# driver.net
KiCad netlist of a schematic drawn in EAGLE
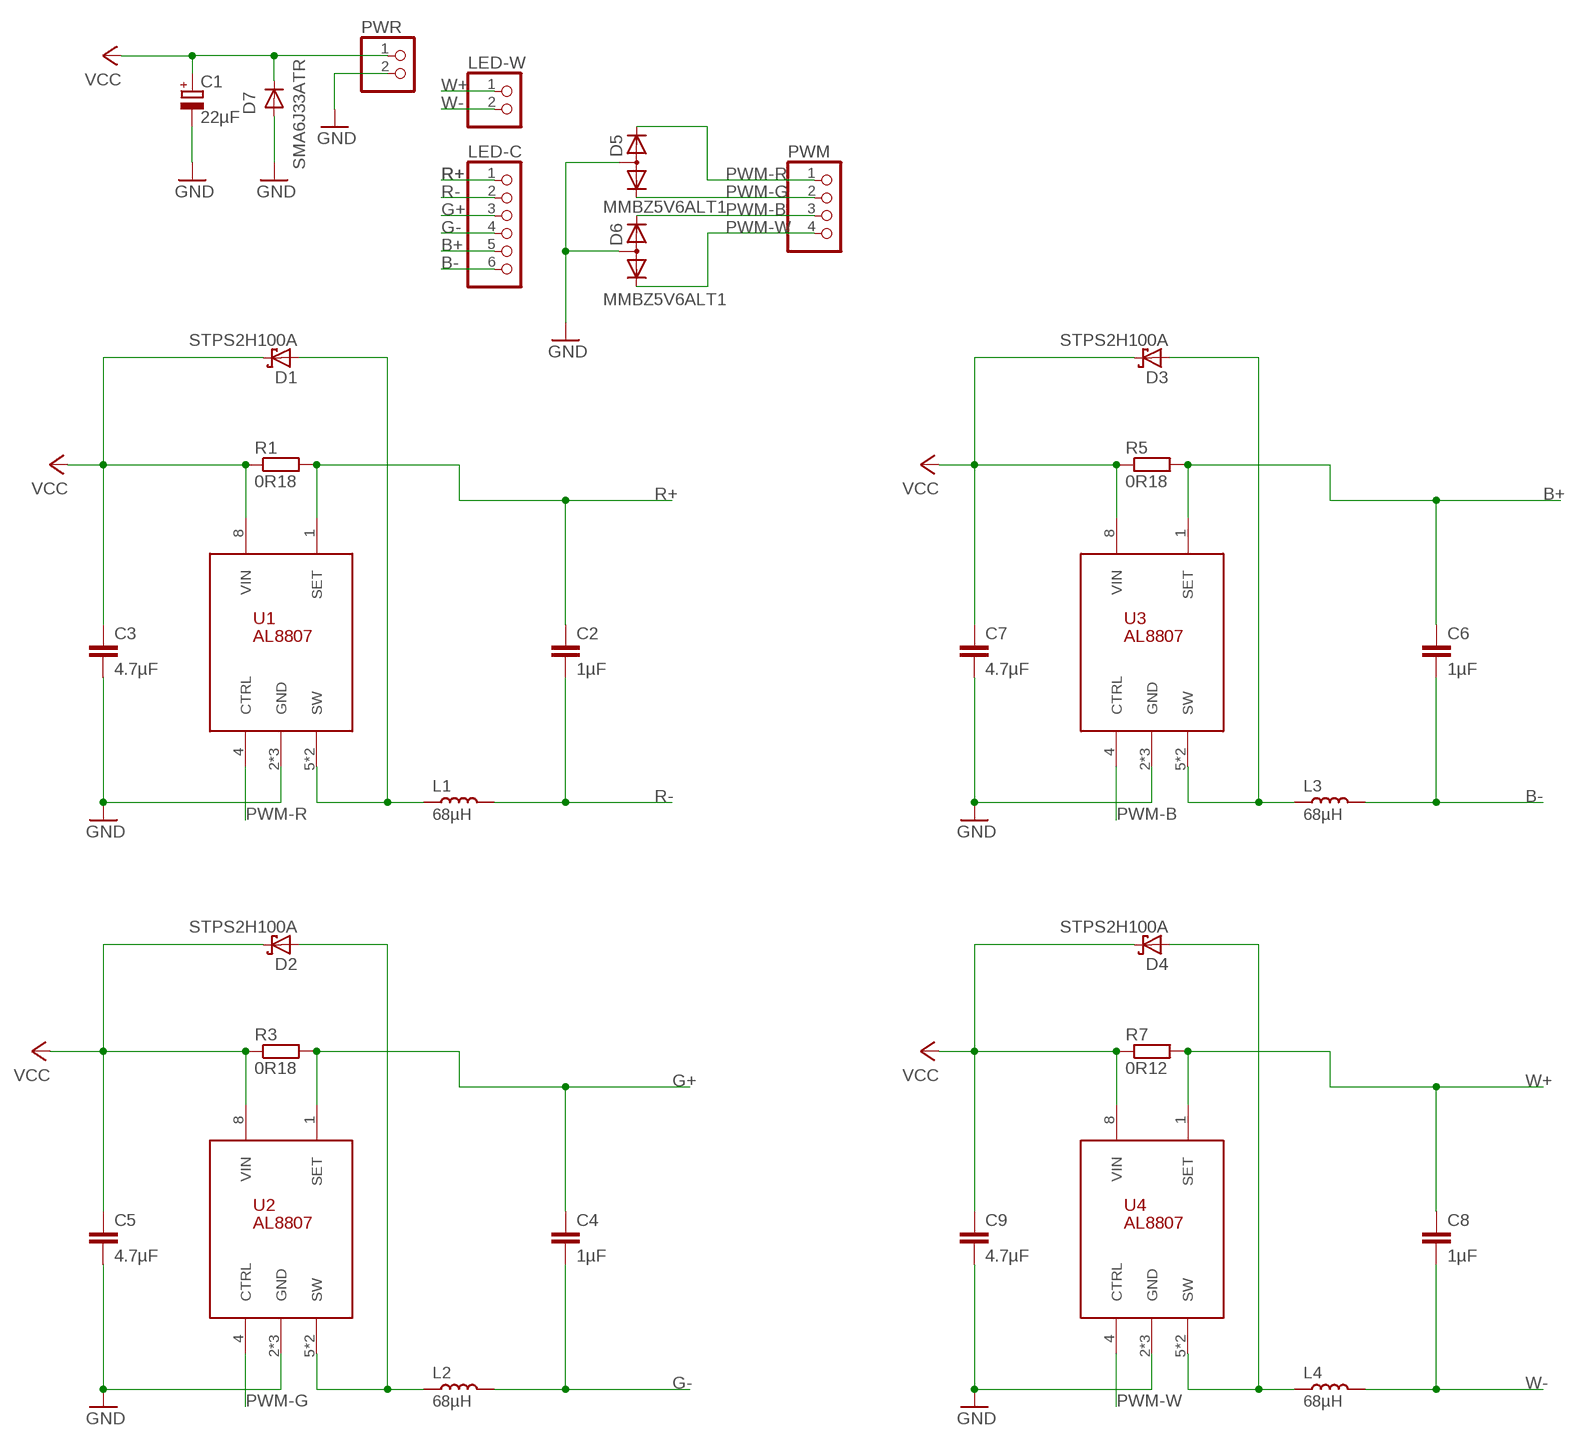
[diagram p0: schematic, sheet 1]

(export (version "E")
  (design (tool "Eeschema 10.0.6"))
  (components
    (comp (ref "C1")
      (value "22µF")
      (footprint "eagle-import:E2-5")
      (libsource (lib "eagle-import") (part "CPOL-EUE2-5"))
    )
    (comp (ref "C2")
      (value "1µF")
      (footprint "eagle-import:C1206")
      (libsource (lib "eagle-import") (part "C-EUC1206"))
    )
    (comp (ref "C3")
      (value "4.7µF")
      (footprint "eagle-import:C1206")
      (libsource (lib "eagle-import") (part "C-EUC1206"))
    )
    (comp (ref "C4")
      (value "1µF")
      (footprint "eagle-import:C1206")
      (libsource (lib "eagle-import") (part "C-EUC1206"))
    )
    (comp (ref "C5")
      (value "4.7µF")
      (footprint "eagle-import:C1206")
      (libsource (lib "eagle-import") (part "C-EUC1206"))
    )
    (comp (ref "C6")
      (value "1µF")
      (footprint "eagle-import:C1206")
      (libsource (lib "eagle-import") (part "C-EUC1206"))
    )
    (comp (ref "C7")
      (value "4.7µF")
      (footprint "eagle-import:C1206")
      (libsource (lib "eagle-import") (part "C-EUC1206"))
    )
    (comp (ref "C8")
      (value "1µF")
      (footprint "eagle-import:C1206")
      (libsource (lib "eagle-import") (part "C-EUC1206"))
    )
    (comp (ref "C9")
      (value "4.7µF")
      (footprint "eagle-import:C1206")
      (libsource (lib "eagle-import") (part "C-EUC1206"))
    )
    (comp (ref "D1")
      (value "STPS2H100A")
      (footprint "eagle-import:ST-DO-214AC")
      (fields (field (name "FARNELL_PART_NUMBER") "1467551"))
      (libsource (lib "eagle-import") (part "STPS2H100A"))
    )
    (comp (ref "D2")
      (value "STPS2H100A")
      (footprint "eagle-import:ST-DO-214AC")
      (fields (field (name "FARNELL_PART_NUMBER") "1467551"))
      (libsource (lib "eagle-import") (part "STPS2H100A"))
    )
    (comp (ref "D3")
      (value "STPS2H100A")
      (footprint "eagle-import:ST-DO-214AC")
      (fields (field (name "FARNELL_PART_NUMBER") "1467551"))
      (libsource (lib "eagle-import") (part "STPS2H100A"))
    )
    (comp (ref "D4")
      (value "STPS2H100A")
      (footprint "eagle-import:ST-DO-214AC")
      (fields (field (name "FARNELL_PART_NUMBER") "1467551"))
      (libsource (lib "eagle-import") (part "STPS2H100A"))
    )
    (comp (ref "D5")
      (value "MMBZ5V6ALT1")
      (footprint "eagle-import:SOT23")
      (libsource (lib "eagle-import") (part "DIODE-2CA|ACSOT23"))
    )
    (comp (ref "D6")
      (value "MMBZ5V6ALT1")
      (footprint "eagle-import:SOT23")
      (libsource (lib "eagle-import") (part "DIODE-2CA|ACSOT23"))
    )
    (comp (ref "D7")
      (value "SMA6J33ATR")
      (footprint "eagle-import:DO-214AC")
      (libsource (lib "eagle-import") (part "DIODE-DO-214AC"))
    )
    (comp (ref "L1")
      (value "68µH")
      (footprint "eagle-import:SRR1260")
      (libsource (lib "eagle-import") (part "INDUCTOR-SRR1260"))
    )
    (comp (ref "L2")
      (value "68µH")
      (footprint "eagle-import:SRR1260")
      (libsource (lib "eagle-import") (part "INDUCTOR-SRR1260"))
    )
    (comp (ref "L3")
      (value "68µH")
      (footprint "eagle-import:SRR1260")
      (libsource (lib "eagle-import") (part "INDUCTOR-SRR1260"))
    )
    (comp (ref "L4")
      (value "68µH")
      (footprint "eagle-import:SRR1260")
      (libsource (lib "eagle-import") (part "INDUCTOR-SRR1260"))
    )
    (comp (ref "LED-C")
      (value "PINHD-1X6")
      (footprint "eagle-import:1X06")
      (libsource (lib "eagle-import") (part "PINHD-1X6"))
    )
    (comp (ref "LED-W")
      (value "PINHD-1X2")
      (footprint "eagle-import:1X02")
      (libsource (lib "eagle-import") (part "PINHD-1X2"))
    )
    (comp (ref "PWM")
      (value "PINHD-1X4")
      (footprint "eagle-import:1X04")
      (libsource (lib "eagle-import") (part "PINHD-1X4"))
    )
    (comp (ref "PWR")
      (value "PINHD-1X2")
      (footprint "eagle-import:1X02")
      (libsource (lib "eagle-import") (part "PINHD-1X2"))
    )
    (comp (ref "R1")
      (value "0R18")
      (footprint "eagle-import:R0805")
      (libsource (lib "eagle-import") (part "R-EU_R0805"))
    )
    (comp (ref "R3")
      (value "0R18")
      (footprint "eagle-import:R0805")
      (libsource (lib "eagle-import") (part "R-EU_R0805"))
    )
    (comp (ref "R5")
      (value "0R18")
      (footprint "eagle-import:R0805")
      (libsource (lib "eagle-import") (part "R-EU_R0805"))
    )
    (comp (ref "R7")
      (value "0R12")
      (footprint "eagle-import:R0805")
      (libsource (lib "eagle-import") (part "R-EU_R0805"))
    )
    (comp (ref "U1")
      (value "AL8807")
      (footprint "eagle-import:MSOP-8EP")
      (libsource (lib "eagle-import") (part "AL8807"))
    )
    (comp (ref "U2")
      (value "AL8807")
      (footprint "eagle-import:MSOP-8EP")
      (libsource (lib "eagle-import") (part "AL8807"))
    )
    (comp (ref "U3")
      (value "AL8807")
      (footprint "eagle-import:MSOP-8EP")
      (libsource (lib "eagle-import") (part "AL8807"))
    )
    (comp (ref "U4")
      (value "AL8807")
      (footprint "eagle-import:MSOP-8EP")
      (libsource (lib "eagle-import") (part "AL8807"))
    )
  )
  (nets
    (net (code "1") (name "/B+") (class "Default")
      (node (ref "C6") (pin "1") (pinfunction "1_1") (pintype "passive"))
      (node (ref "LED-C") (pin "5") (pinfunction "5_5") (pintype "passive"))
      (node (ref "R5") (pin "2") (pinfunction "2_2") (pintype "passive"))
      (node (ref "U3") (pin "1") (pinfunction "SET_1") (pintype "bidirectional"))
    )
    (net (code "2") (name "/B-") (class "Default")
      (node (ref "C6") (pin "2") (pinfunction "2_2") (pintype "passive"))
      (node (ref "L3") (pin "2") (pinfunction "2_2") (pintype "passive"))
      (node (ref "LED-C") (pin "6") (pinfunction "6_6") (pintype "passive"))
    )
    (net (code "3") (name "/G+") (class "Default")
      (node (ref "C4") (pin "1") (pinfunction "1_1") (pintype "passive"))
      (node (ref "LED-C") (pin "3") (pinfunction "3_3") (pintype "passive"))
      (node (ref "R3") (pin "2") (pinfunction "2_2") (pintype "passive"))
      (node (ref "U2") (pin "1") (pinfunction "SET_1") (pintype "bidirectional"))
    )
    (net (code "4") (name "/G-") (class "Default")
      (node (ref "C4") (pin "2") (pinfunction "2_2") (pintype "passive"))
      (node (ref "L2") (pin "2") (pinfunction "2_2") (pintype "passive"))
      (node (ref "LED-C") (pin "4") (pinfunction "4_4") (pintype "passive"))
    )
    (net (code "5") (name "/PWM-B") (class "Default")
      (node (ref "D6") (pin "2") (pinfunction "K2_2") (pintype "passive"))
      (node (ref "PWM") (pin "3") (pinfunction "3_3") (pintype "passive"))
      (node (ref "U3") (pin "4") (pinfunction "CTRL_4") (pintype "bidirectional"))
    )
    (net (code "6") (name "/PWM-G") (class "Default")
      (node (ref "D5") (pin "1") (pinfunction "K1_1") (pintype "passive"))
      (node (ref "PWM") (pin "2") (pinfunction "2_2") (pintype "passive"))
      (node (ref "U2") (pin "4") (pinfunction "CTRL_4") (pintype "bidirectional"))
    )
    (net (code "7") (name "/PWM-R") (class "Default")
      (node (ref "D5") (pin "2") (pinfunction "K2_2") (pintype "passive"))
      (node (ref "PWM") (pin "1") (pinfunction "1_1") (pintype "passive"))
      (node (ref "U1") (pin "4") (pinfunction "CTRL_4") (pintype "bidirectional"))
    )
    (net (code "8") (name "/PWM-W") (class "Default")
      (node (ref "D6") (pin "1") (pinfunction "K1_1") (pintype "passive"))
      (node (ref "PWM") (pin "4") (pinfunction "4_4") (pintype "passive"))
      (node (ref "U4") (pin "4") (pinfunction "CTRL_4") (pintype "bidirectional"))
    )
    (net (code "9") (name "/R+") (class "Default")
      (node (ref "C2") (pin "1") (pinfunction "1_1") (pintype "passive"))
      (node (ref "LED-C") (pin "1") (pinfunction "1_1") (pintype "passive"))
      (node (ref "R1") (pin "2") (pinfunction "2_2") (pintype "passive"))
      (node (ref "U1") (pin "1") (pinfunction "SET_1") (pintype "bidirectional"))
    )
    (net (code "10") (name "/R-") (class "Default")
      (node (ref "C2") (pin "2") (pinfunction "2_2") (pintype "passive"))
      (node (ref "L1") (pin "2") (pinfunction "2_2") (pintype "passive"))
      (node (ref "LED-C") (pin "2") (pinfunction "2_2") (pintype "passive"))
    )
    (net (code "11") (name "/W+") (class "Default")
      (node (ref "C8") (pin "1") (pinfunction "1_1") (pintype "passive"))
      (node (ref "LED-W") (pin "1") (pinfunction "1_1") (pintype "passive"))
      (node (ref "R7") (pin "2") (pinfunction "2_2") (pintype "passive"))
      (node (ref "U4") (pin "1") (pinfunction "SET_1") (pintype "bidirectional"))
    )
    (net (code "12") (name "/W-") (class "Default")
      (node (ref "C8") (pin "2") (pinfunction "2_2") (pintype "passive"))
      (node (ref "L4") (pin "2") (pinfunction "2_2") (pintype "passive"))
      (node (ref "LED-W") (pin "2") (pinfunction "2_2") (pintype "passive"))
    )
    (net (code "13") (name "GND") (class "Default")
      (node (ref "C1") (pin "-") (pinfunction "-_-") (pintype "passive"))
      (node (ref "C3") (pin "2") (pinfunction "2_2") (pintype "passive"))
      (node (ref "C5") (pin "2") (pinfunction "2_2") (pintype "passive"))
      (node (ref "C7") (pin "2") (pinfunction "2_2") (pintype "passive"))
      (node (ref "C9") (pin "2") (pinfunction "2_2") (pintype "passive"))
      (node (ref "D5") (pin "3") (pinfunction "A_3") (pintype "passive"))
      (node (ref "D6") (pin "3") (pinfunction "A_3") (pintype "passive"))
      (node (ref "D7") (pin "A") (pinfunction "A_A") (pintype "passive"))
      (node (ref "PWR") (pin "2") (pinfunction "2_2") (pintype "passive"))
      (node (ref "U1") (pin "2") (pinfunction "GND_2") (pintype "bidirectional"))
      (node (ref "U1") (pin "3") (pinfunction "GND_3") (pintype "bidirectional"))
      (node (ref "U1") (pin "9") (pinfunction "GND_9") (pintype "bidirectional"))
      (node (ref "U2") (pin "2") (pinfunction "GND_2") (pintype "bidirectional"))
      (node (ref "U2") (pin "3") (pinfunction "GND_3") (pintype "bidirectional"))
      (node (ref "U2") (pin "9") (pinfunction "GND_9") (pintype "bidirectional"))
      (node (ref "U3") (pin "2") (pinfunction "GND_2") (pintype "bidirectional"))
      (node (ref "U3") (pin "3") (pinfunction "GND_3") (pintype "bidirectional"))
      (node (ref "U3") (pin "9") (pinfunction "GND_9") (pintype "bidirectional"))
      (node (ref "U4") (pin "2") (pinfunction "GND_2") (pintype "bidirectional"))
      (node (ref "U4") (pin "3") (pinfunction "GND_3") (pintype "bidirectional"))
      (node (ref "U4") (pin "9") (pinfunction "GND_9") (pintype "bidirectional"))
    )
    (net (code "14") (name "Net-(D1-PadA)") (class "Default")
      (node (ref "D1") (pin "A") (pinfunction "A_A") (pintype "passive"))
      (node (ref "L1") (pin "1") (pinfunction "1_1") (pintype "passive"))
      (node (ref "U1") (pin "5") (pinfunction "SW_5") (pintype "bidirectional"))
      (node (ref "U1") (pin "6") (pinfunction "SW_6") (pintype "bidirectional"))
    )
    (net (code "15") (name "Net-(D2-PadA)") (class "Default")
      (node (ref "D2") (pin "A") (pinfunction "A_A") (pintype "passive"))
      (node (ref "L2") (pin "1") (pinfunction "1_1") (pintype "passive"))
      (node (ref "U2") (pin "5") (pinfunction "SW_5") (pintype "bidirectional"))
      (node (ref "U2") (pin "6") (pinfunction "SW_6") (pintype "bidirectional"))
    )
    (net (code "16") (name "Net-(D3-PadA)") (class "Default")
      (node (ref "D3") (pin "A") (pinfunction "A_A") (pintype "passive"))
      (node (ref "L3") (pin "1") (pinfunction "1_1") (pintype "passive"))
      (node (ref "U3") (pin "5") (pinfunction "SW_5") (pintype "bidirectional"))
      (node (ref "U3") (pin "6") (pinfunction "SW_6") (pintype "bidirectional"))
    )
    (net (code "17") (name "Net-(D4-PadA)") (class "Default")
      (node (ref "D4") (pin "A") (pinfunction "A_A") (pintype "passive"))
      (node (ref "L4") (pin "1") (pinfunction "1_1") (pintype "passive"))
      (node (ref "U4") (pin "5") (pinfunction "SW_5") (pintype "bidirectional"))
      (node (ref "U4") (pin "6") (pinfunction "SW_6") (pintype "bidirectional"))
    )
    (net (code "18") (name "VCC") (class "Default")
      (node (ref "C1") (pin "+") (pinfunction "+_+") (pintype "passive"))
      (node (ref "C3") (pin "1") (pinfunction "1_1") (pintype "passive"))
      (node (ref "C5") (pin "1") (pinfunction "1_1") (pintype "passive"))
      (node (ref "C7") (pin "1") (pinfunction "1_1") (pintype "passive"))
      (node (ref "C9") (pin "1") (pinfunction "1_1") (pintype "passive"))
      (node (ref "D1") (pin "C") (pinfunction "C_C") (pintype "passive"))
      (node (ref "D2") (pin "C") (pinfunction "C_C") (pintype "passive"))
      (node (ref "D3") (pin "C") (pinfunction "C_C") (pintype "passive"))
      (node (ref "D4") (pin "C") (pinfunction "C_C") (pintype "passive"))
      (node (ref "D7") (pin "C") (pinfunction "C_C") (pintype "passive"))
      (node (ref "PWR") (pin "1") (pinfunction "1_1") (pintype "passive"))
      (node (ref "R1") (pin "1") (pinfunction "1_1") (pintype "passive"))
      (node (ref "R3") (pin "1") (pinfunction "1_1") (pintype "passive"))
      (node (ref "R5") (pin "1") (pinfunction "1_1") (pintype "passive"))
      (node (ref "R7") (pin "1") (pinfunction "1_1") (pintype "passive"))
      (node (ref "U1") (pin "8") (pinfunction "VIN_8") (pintype "bidirectional"))
      (node (ref "U2") (pin "8") (pinfunction "VIN_8") (pintype "bidirectional"))
      (node (ref "U3") (pin "8") (pinfunction "VIN_8") (pintype "bidirectional"))
      (node (ref "U4") (pin "8") (pinfunction "VIN_8") (pintype "bidirectional"))
    )
  )
)
